# pisarnaInGarderoba-v2.net
KiCad netlist of a schematic drawn in EAGLE
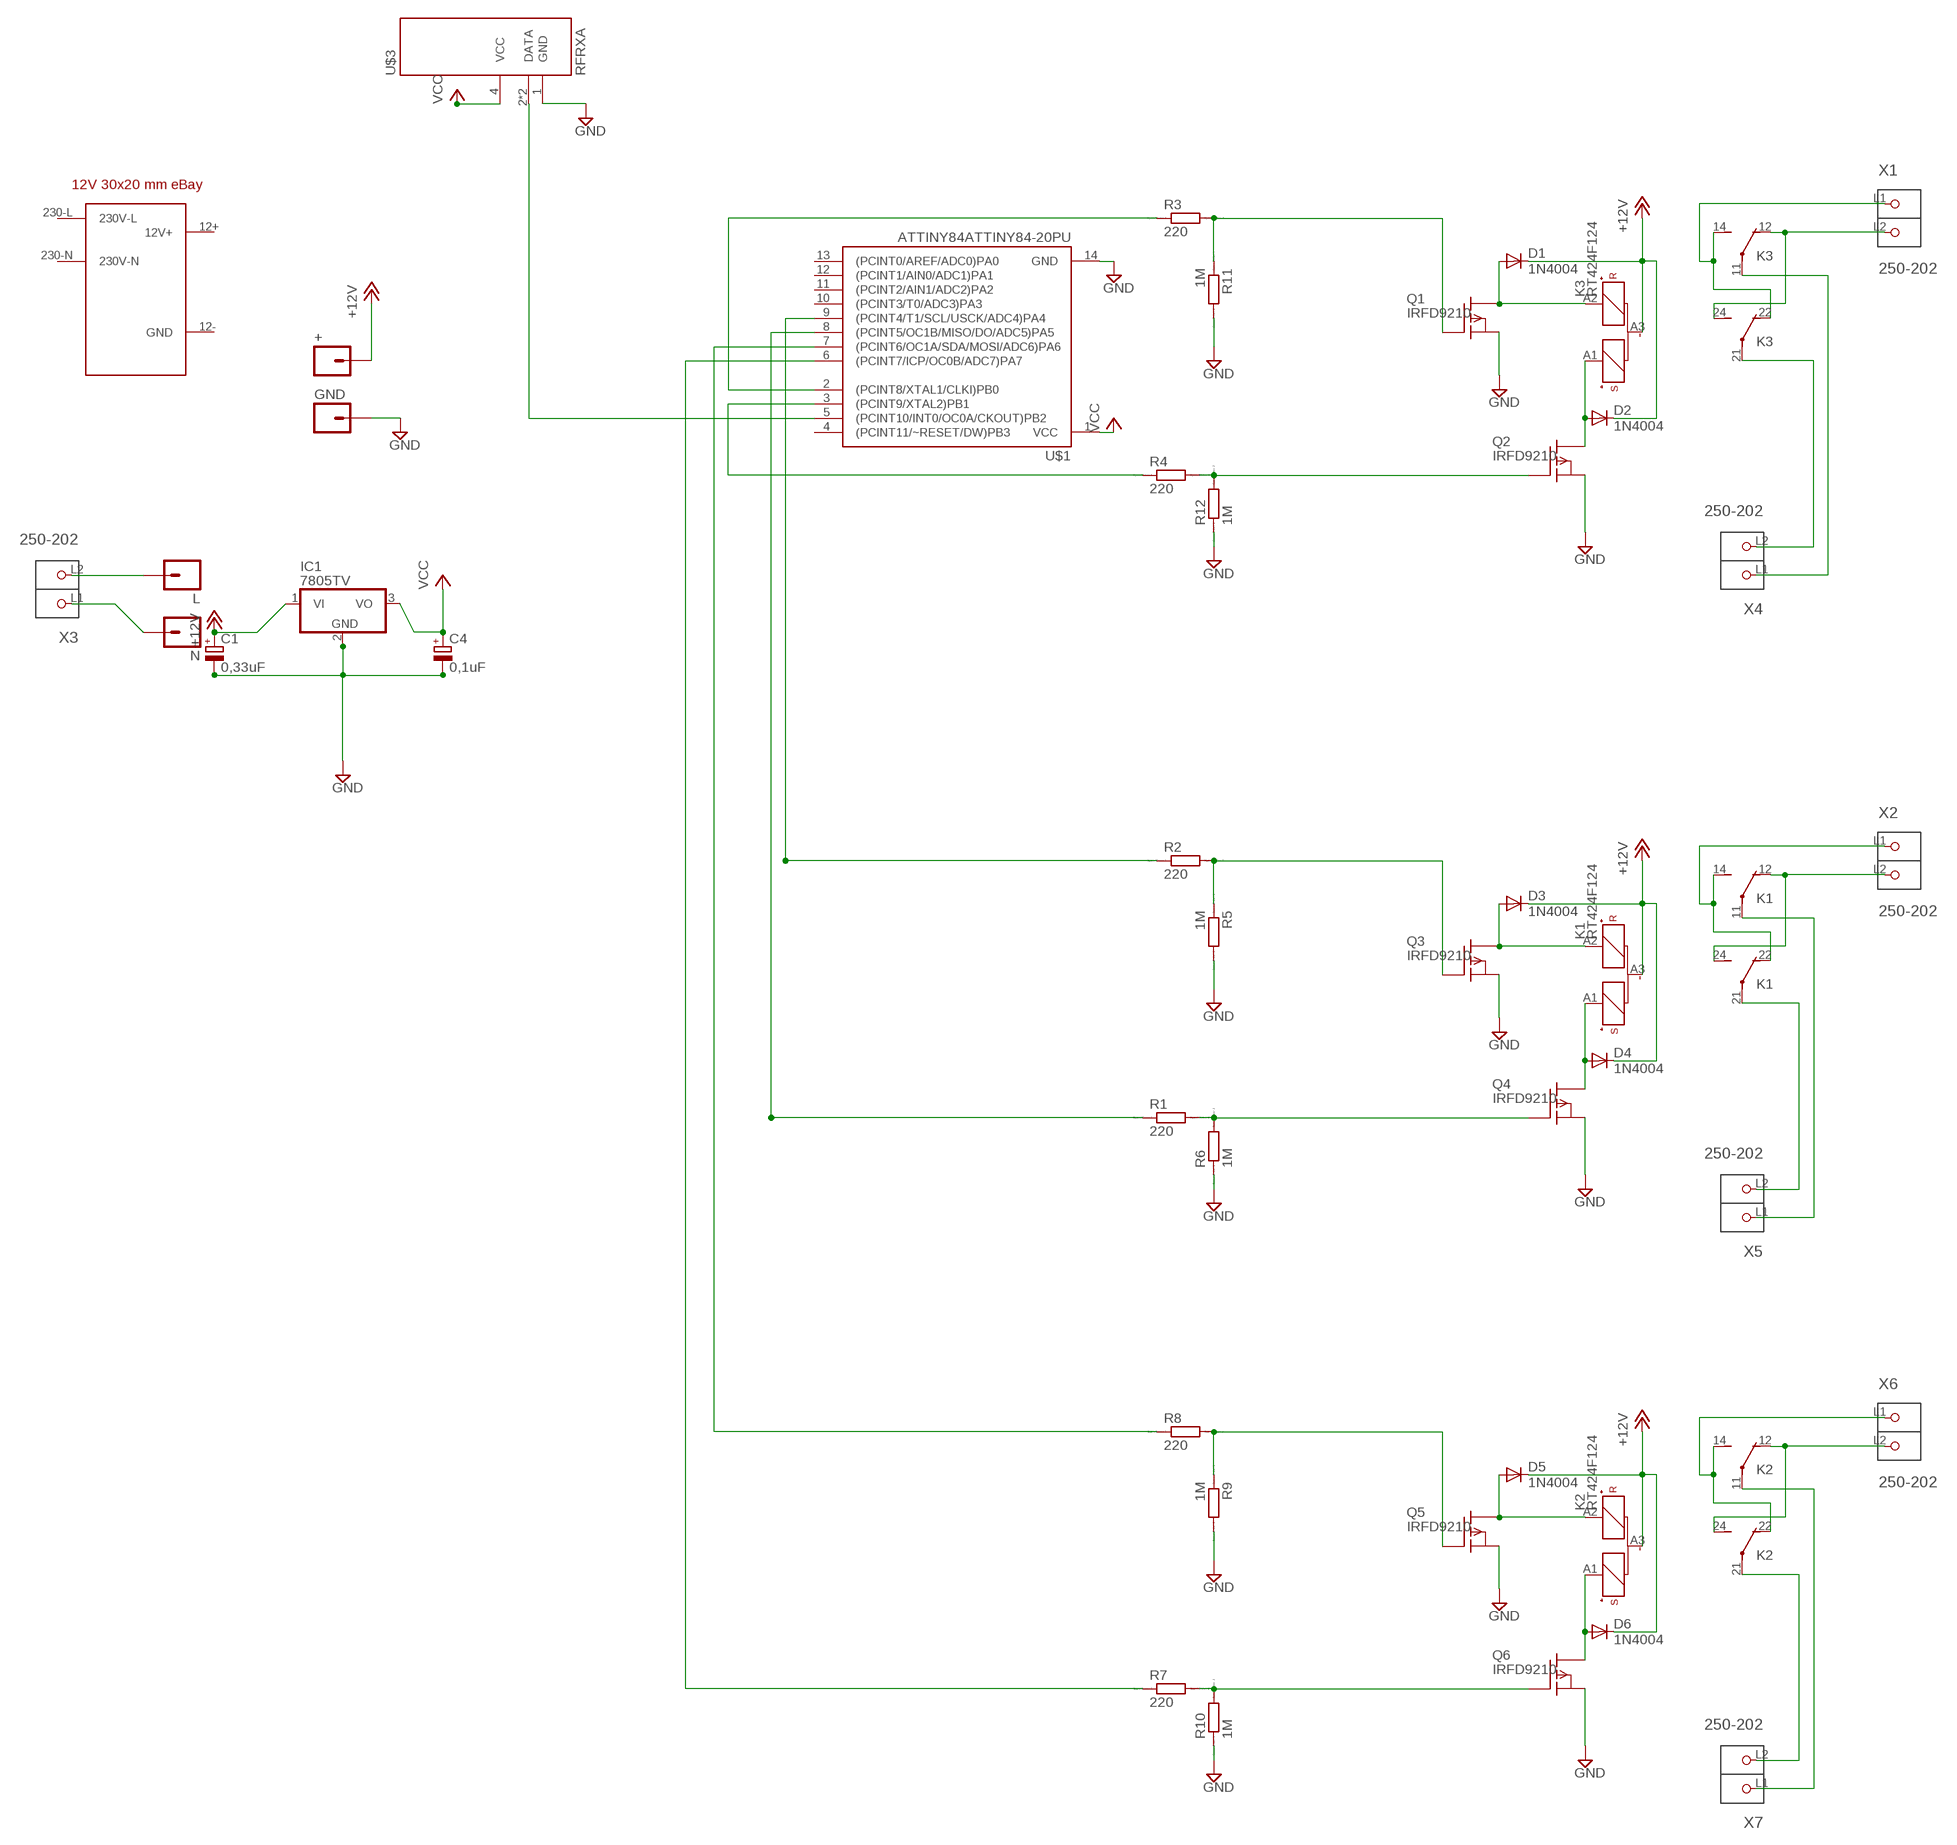
[diagram p0: schematic, sheet 1, part 1 of 2]
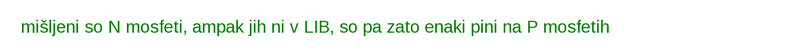
[diagram p1: schematic, sheet 1, part 2 of 2]

(export (version "E")
  (design (tool "Eeschema 10.0.6"))
  (components
    (comp (ref "+")
      (value "M01PTH")
      (footprint "eagle-import:1X01")
      (libsource (lib "eagle-import") (part "M01PTH"))
    )
    (comp (ref "C1")
      (value "0,33uF")
      (footprint "eagle-import:E2,5-5")
      (fields (field (name "MF") "SPC TECHNOLOGY") (field (name "MPN") "SPC15391"))
      (libsource (lib "eagle-import") (part "CPOL-EUE2.5-5"))
    )
    (comp (ref "C4")
      (value "0,1uF")
      (footprint "eagle-import:E2,5-5")
      (fields (field (name "MF") "SPC TECHNOLOGY") (field (name "MPN") "SPC15391"))
      (libsource (lib "eagle-import") (part "CPOL-EUE2.5-5"))
    )
    (comp (ref "D1")
      (value "1N4004")
      (footprint "eagle-import:DO41-10")
      (libsource (lib "eagle-import") (part "1N4004"))
    )
    (comp (ref "D2")
      (value "1N4004")
      (footprint "eagle-import:DO41-10")
      (libsource (lib "eagle-import") (part "1N4004"))
    )
    (comp (ref "D3")
      (value "1N4004")
      (footprint "eagle-import:DO41-10")
      (libsource (lib "eagle-import") (part "1N4004"))
    )
    (comp (ref "D4")
      (value "1N4004")
      (footprint "eagle-import:DO41-10")
      (libsource (lib "eagle-import") (part "1N4004"))
    )
    (comp (ref "D5")
      (value "1N4004")
      (footprint "eagle-import:DO41-10")
      (libsource (lib "eagle-import") (part "1N4004"))
    )
    (comp (ref "D6")
      (value "1N4004")
      (footprint "eagle-import:DO41-10")
      (libsource (lib "eagle-import") (part "1N4004"))
    )
    (comp (ref "GND")
      (value "M01PTH")
      (footprint "eagle-import:1X01")
      (libsource (lib "eagle-import") (part "M01PTH"))
    )
    (comp (ref "IC1")
      (value "7805TV")
      (footprint "eagle-import:TO220V")
      (libsource (lib "eagle-import") (part "78TV05"))
    )
    (comp (ref "K1")
      (value "RT424F124")
      (footprint "eagle-import:RT424")
      (libsource (lib "eagle-import") (part "RT424F412"))
    )
    (comp (ref "K2")
      (value "RT424F124")
      (footprint "eagle-import:RT424")
      (libsource (lib "eagle-import") (part "RT424F412"))
    )
    (comp (ref "K3")
      (value "RT424F124")
      (footprint "eagle-import:RT424")
      (libsource (lib "eagle-import") (part "RT424F412"))
    )
    (comp (ref "L")
      (value "M01PTH")
      (footprint "eagle-import:1X01")
      (libsource (lib "eagle-import") (part "M01PTH"))
    )
    (comp (ref "N")
      (value "M01PTH")
      (footprint "eagle-import:1X01")
      (libsource (lib "eagle-import") (part "M01PTH"))
    )
    (comp (ref "Q1")
      (value "IRFD9210")
      (footprint "eagle-import:DIL04")
      (libsource (lib "eagle-import") (part "IRFD9210"))
    )
    (comp (ref "Q2")
      (value "IRFD9210")
      (footprint "eagle-import:DIL04")
      (libsource (lib "eagle-import") (part "IRFD9210"))
    )
    (comp (ref "Q3")
      (value "IRFD9210")
      (footprint "eagle-import:DIL04")
      (libsource (lib "eagle-import") (part "IRFD9210"))
    )
    (comp (ref "Q4")
      (value "IRFD9210")
      (footprint "eagle-import:DIL04")
      (libsource (lib "eagle-import") (part "IRFD9210"))
    )
    (comp (ref "Q5")
      (value "IRFD9210")
      (footprint "eagle-import:DIL04")
      (libsource (lib "eagle-import") (part "IRFD9210"))
    )
    (comp (ref "Q6")
      (value "IRFD9210")
      (footprint "eagle-import:DIL04")
      (libsource (lib "eagle-import") (part "IRFD9210"))
    )
    (comp (ref "R1")
      (value "220")
      (footprint "eagle-import:0204_7")
      (libsource (lib "eagle-import") (part "R0204/7"))
    )
    (comp (ref "R2")
      (value "220")
      (footprint "eagle-import:0204_7")
      (libsource (lib "eagle-import") (part "R0204/7"))
    )
    (comp (ref "R3")
      (value "220")
      (footprint "eagle-import:0204_7")
      (libsource (lib "eagle-import") (part "R0204/7"))
    )
    (comp (ref "R4")
      (value "220")
      (footprint "eagle-import:0204_7")
      (libsource (lib "eagle-import") (part "R0204/7"))
    )
    (comp (ref "R5")
      (value "1M")
      (footprint "eagle-import:0204_7")
      (libsource (lib "eagle-import") (part "R0204/7"))
    )
    (comp (ref "R6")
      (value "1M")
      (footprint "eagle-import:0204_7")
      (libsource (lib "eagle-import") (part "R0204/7"))
    )
    (comp (ref "R7")
      (value "220")
      (footprint "eagle-import:0204_7")
      (libsource (lib "eagle-import") (part "R0204/7"))
    )
    (comp (ref "R8")
      (value "220")
      (footprint "eagle-import:0204_7")
      (libsource (lib "eagle-import") (part "R0204/7"))
    )
    (comp (ref "R9")
      (value "1M")
      (footprint "eagle-import:0204_7")
      (libsource (lib "eagle-import") (part "R0204/7"))
    )
    (comp (ref "R10")
      (value "1M")
      (footprint "eagle-import:0204_7")
      (libsource (lib "eagle-import") (part "R0204/7"))
    )
    (comp (ref "R11")
      (value "1M")
      (footprint "eagle-import:0204_7")
      (libsource (lib "eagle-import") (part "R0204/7"))
    )
    (comp (ref "R12")
      (value "1M")
      (footprint "eagle-import:0204_7")
      (libsource (lib "eagle-import") (part "R0204/7"))
    )
    (comp (ref "U$1")
      (value "ATTINY84ATTINY84-20PU")
      (footprint "eagle-import:DIL14")
      (libsource (lib "eagle-import") (part "ATTINY84ATTINY84-20PU"))
    )
    (comp (ref "U$2")
      (value "12V-30X20")
      (footprint "eagle-import:12V30X20")
      (libsource (lib "eagle-import") (part "12V-30X20"))
    )
    (comp (ref "U$3")
      (value "RFRXA")
      (footprint "eagle-import:IC")
      (libsource (lib "eagle-import") (part "RFRXA"))
    )
    (comp (ref "X1")
      (value "250-202")
      (footprint "eagle-import:P-250-202")
      (libsource (lib "eagle-import") (part "250-202"))
    )
    (comp (ref "X2")
      (value "250-202")
      (footprint "eagle-import:P-250-202")
      (libsource (lib "eagle-import") (part "250-202"))
    )
    (comp (ref "X3")
      (value "250-202")
      (footprint "eagle-import:P-250-202")
      (libsource (lib "eagle-import") (part "250-202"))
    )
    (comp (ref "X4")
      (value "250-202")
      (footprint "eagle-import:P-250-202")
      (libsource (lib "eagle-import") (part "250-202"))
    )
    (comp (ref "X5")
      (value "250-202")
      (footprint "eagle-import:P-250-202")
      (libsource (lib "eagle-import") (part "250-202"))
    )
    (comp (ref "X6")
      (value "250-202")
      (footprint "eagle-import:P-250-202")
      (libsource (lib "eagle-import") (part "250-202"))
    )
    (comp (ref "X7")
      (value "250-202")
      (footprint "eagle-import:P-250-202")
      (libsource (lib "eagle-import") (part "250-202"))
    )
  )
  (nets
    (net (code "1") (name "+12V") (class "Default")
      (node (ref "+") (pin "1") (pinfunction "1_1") (pintype "passive"))
      (node (ref "C1") (pin "+") (pinfunction "+_+") (pintype "passive"))
      (node (ref "D1") (pin "C") (pinfunction "C_C") (pintype "passive"))
      (node (ref "D2") (pin "C") (pinfunction "C_C") (pintype "passive"))
      (node (ref "D3") (pin "C") (pinfunction "C_C") (pintype "passive"))
      (node (ref "D4") (pin "C") (pinfunction "C_C") (pintype "passive"))
      (node (ref "D5") (pin "C") (pinfunction "C_C") (pintype "passive"))
      (node (ref "D6") (pin "C") (pinfunction "C_C") (pintype "passive"))
      (node (ref "IC1") (pin "1") (pinfunction "VI_1") (pintype "input"))
      (node (ref "K1") (pin "A3") (pinfunction "-_A3") (pintype "passive"))
      (node (ref "K2") (pin "A3") (pinfunction "-_A3") (pintype "passive"))
      (node (ref "K3") (pin "A3") (pinfunction "-_A3") (pintype "passive"))
    )
    (net (code "2") (name "GND") (class "Default")
      (node (ref "C1") (pin "-") (pinfunction "-_-") (pintype "passive"))
      (node (ref "C4") (pin "-") (pinfunction "-_-") (pintype "passive"))
      (node (ref "GND") (pin "1") (pinfunction "1_1") (pintype "passive"))
      (node (ref "IC1") (pin "2") (pinfunction "GND_2") (pintype "passive"))
      (node (ref "Q1") (pin "2") (pinfunction "S_2") (pintype "passive"))
      (node (ref "Q2") (pin "2") (pinfunction "S_2") (pintype "passive"))
      (node (ref "Q3") (pin "2") (pinfunction "S_2") (pintype "passive"))
      (node (ref "Q4") (pin "2") (pinfunction "S_2") (pintype "passive"))
      (node (ref "Q5") (pin "2") (pinfunction "S_2") (pintype "passive"))
      (node (ref "Q6") (pin "2") (pinfunction "S_2") (pintype "passive"))
      (node (ref "R10") (pin "1") (pinfunction "1_1") (pintype "passive"))
      (node (ref "R11") (pin "2") (pinfunction "2_2") (pintype "passive"))
      (node (ref "R12") (pin "1") (pinfunction "1_1") (pintype "passive"))
      (node (ref "R5") (pin "2") (pinfunction "2_2") (pintype "passive"))
      (node (ref "R6") (pin "1") (pinfunction "1_1") (pintype "passive"))
      (node (ref "R9") (pin "2") (pinfunction "2_2") (pintype "passive"))
      (node (ref "U$1") (pin "14") (pinfunction "GND_14") (pintype "bidirectional"))
      (node (ref "U$3") (pin "1") (pinfunction "GND_1") (pintype "bidirectional"))
    )
    (net (code "3") (name "Net-(K1A-R+)") (class "Default")
      (node (ref "D3") (pin "A") (pinfunction "A_A") (pintype "passive"))
      (node (ref "K1") (pin "A2") (pinfunction "R+_A2") (pintype "passive"))
      (node (ref "Q3") (pin "3") (pinfunction "D_3") (pintype "passive"))
      (node (ref "Q3") (pin "4") (pinfunction "D_4") (pintype "passive"))
    )
    (net (code "4") (name "Net-(K1A-S+)") (class "Default")
      (node (ref "D4") (pin "A") (pinfunction "A_A") (pintype "passive"))
      (node (ref "K1") (pin "A1") (pinfunction "S+_A1") (pintype "passive"))
      (node (ref "Q4") (pin "3") (pinfunction "D_3") (pintype "passive"))
      (node (ref "Q4") (pin "4") (pinfunction "D_4") (pintype "passive"))
    )
    (net (code "5") (name "Net-(K1B-O)") (class "Default")
      (node (ref "K1") (pin "12") (pinfunction "O_12") (pintype "passive"))
      (node (ref "K1") (pin "24") (pinfunction "S_24") (pintype "passive"))
      (node (ref "X2") (pin "L2") (pinfunction "P2_L2") (pintype "bidirectional"))
    )
    (net (code "6") (name "Net-(K1B-P)") (class "Default")
      (node (ref "K1") (pin "11") (pinfunction "P_11") (pintype "passive"))
      (node (ref "X5") (pin "L1") (pinfunction "P1_L1") (pintype "bidirectional"))
    )
    (net (code "7") (name "Net-(K1B-S)") (class "Default")
      (node (ref "K1") (pin "14") (pinfunction "S_14") (pintype "passive"))
      (node (ref "K1") (pin "22") (pinfunction "O_22") (pintype "passive"))
      (node (ref "X2") (pin "L1") (pinfunction "P1_L1") (pintype "bidirectional"))
    )
    (net (code "8") (name "Net-(K1C-P)") (class "Default")
      (node (ref "K1") (pin "21") (pinfunction "P_21") (pintype "passive"))
      (node (ref "X5") (pin "L2") (pinfunction "P2_L2") (pintype "bidirectional"))
    )
    (net (code "9") (name "Net-(K2A-R+)") (class "Default")
      (node (ref "D5") (pin "A") (pinfunction "A_A") (pintype "passive"))
      (node (ref "K2") (pin "A2") (pinfunction "R+_A2") (pintype "passive"))
      (node (ref "Q5") (pin "3") (pinfunction "D_3") (pintype "passive"))
      (node (ref "Q5") (pin "4") (pinfunction "D_4") (pintype "passive"))
    )
    (net (code "10") (name "Net-(K2A-S+)") (class "Default")
      (node (ref "D6") (pin "A") (pinfunction "A_A") (pintype "passive"))
      (node (ref "K2") (pin "A1") (pinfunction "S+_A1") (pintype "passive"))
      (node (ref "Q6") (pin "3") (pinfunction "D_3") (pintype "passive"))
      (node (ref "Q6") (pin "4") (pinfunction "D_4") (pintype "passive"))
    )
    (net (code "11") (name "Net-(K2B-O)") (class "Default")
      (node (ref "K2") (pin "12") (pinfunction "O_12") (pintype "passive"))
      (node (ref "K2") (pin "24") (pinfunction "S_24") (pintype "passive"))
      (node (ref "X6") (pin "L2") (pinfunction "P2_L2") (pintype "bidirectional"))
    )
    (net (code "12") (name "Net-(K2B-P)") (class "Default")
      (node (ref "K2") (pin "11") (pinfunction "P_11") (pintype "passive"))
      (node (ref "X7") (pin "L1") (pinfunction "P1_L1") (pintype "bidirectional"))
    )
    (net (code "13") (name "Net-(K2B-S)") (class "Default")
      (node (ref "K2") (pin "14") (pinfunction "S_14") (pintype "passive"))
      (node (ref "K2") (pin "22") (pinfunction "O_22") (pintype "passive"))
      (node (ref "X6") (pin "L1") (pinfunction "P1_L1") (pintype "bidirectional"))
    )
    (net (code "14") (name "Net-(K2C-P)") (class "Default")
      (node (ref "K2") (pin "21") (pinfunction "P_21") (pintype "passive"))
      (node (ref "X7") (pin "L2") (pinfunction "P2_L2") (pintype "bidirectional"))
    )
    (net (code "15") (name "Net-(K3A-R+)") (class "Default")
      (node (ref "D1") (pin "A") (pinfunction "A_A") (pintype "passive"))
      (node (ref "K3") (pin "A2") (pinfunction "R+_A2") (pintype "passive"))
      (node (ref "Q1") (pin "3") (pinfunction "D_3") (pintype "passive"))
      (node (ref "Q1") (pin "4") (pinfunction "D_4") (pintype "passive"))
    )
    (net (code "16") (name "Net-(K3A-S+)") (class "Default")
      (node (ref "D2") (pin "A") (pinfunction "A_A") (pintype "passive"))
      (node (ref "K3") (pin "A1") (pinfunction "S+_A1") (pintype "passive"))
      (node (ref "Q2") (pin "3") (pinfunction "D_3") (pintype "passive"))
      (node (ref "Q2") (pin "4") (pinfunction "D_4") (pintype "passive"))
    )
    (net (code "17") (name "Net-(K3B-O)") (class "Default")
      (node (ref "K3") (pin "12") (pinfunction "O_12") (pintype "passive"))
      (node (ref "K3") (pin "24") (pinfunction "S_24") (pintype "passive"))
      (node (ref "X1") (pin "L2") (pinfunction "P2_L2") (pintype "bidirectional"))
    )
    (net (code "18") (name "Net-(K3B-P)") (class "Default")
      (node (ref "K3") (pin "11") (pinfunction "P_11") (pintype "passive"))
      (node (ref "X4") (pin "L1") (pinfunction "P1_L1") (pintype "bidirectional"))
    )
    (net (code "19") (name "Net-(K3B-S)") (class "Default")
      (node (ref "K3") (pin "14") (pinfunction "S_14") (pintype "passive"))
      (node (ref "K3") (pin "22") (pinfunction "O_22") (pintype "passive"))
      (node (ref "X1") (pin "L1") (pinfunction "P1_L1") (pintype "bidirectional"))
    )
    (net (code "20") (name "Net-(K3C-P)") (class "Default")
      (node (ref "K3") (pin "21") (pinfunction "P_21") (pintype "passive"))
      (node (ref "X4") (pin "L2") (pinfunction "P2_L2") (pintype "bidirectional"))
    )
    (net (code "21") (name "Net-(Q1-G)") (class "Default")
      (node (ref "Q1") (pin "1") (pinfunction "G_1") (pintype "passive"))
      (node (ref "R11") (pin "1") (pinfunction "1_1") (pintype "passive"))
      (node (ref "R3") (pin "2") (pinfunction "2_2") (pintype "passive"))
    )
    (net (code "22") (name "Net-(Q2-G)") (class "Default")
      (node (ref "Q2") (pin "1") (pinfunction "G_1") (pintype "passive"))
      (node (ref "R12") (pin "2") (pinfunction "2_2") (pintype "passive"))
      (node (ref "R4") (pin "2") (pinfunction "2_2") (pintype "passive"))
    )
    (net (code "23") (name "Net-(Q3-G)") (class "Default")
      (node (ref "Q3") (pin "1") (pinfunction "G_1") (pintype "passive"))
      (node (ref "R2") (pin "2") (pinfunction "2_2") (pintype "passive"))
      (node (ref "R5") (pin "1") (pinfunction "1_1") (pintype "passive"))
    )
    (net (code "24") (name "Net-(Q4-G)") (class "Default")
      (node (ref "Q4") (pin "1") (pinfunction "G_1") (pintype "passive"))
      (node (ref "R1") (pin "2") (pinfunction "2_2") (pintype "passive"))
      (node (ref "R6") (pin "2") (pinfunction "2_2") (pintype "passive"))
    )
    (net (code "25") (name "Net-(Q5-G)") (class "Default")
      (node (ref "Q5") (pin "1") (pinfunction "G_1") (pintype "passive"))
      (node (ref "R8") (pin "2") (pinfunction "2_2") (pintype "passive"))
      (node (ref "R9") (pin "1") (pinfunction "1_1") (pintype "passive"))
    )
    (net (code "26") (name "Net-(Q6-G)") (class "Default")
      (node (ref "Q6") (pin "1") (pinfunction "G_1") (pintype "passive"))
      (node (ref "R10") (pin "2") (pinfunction "2_2") (pintype "passive"))
      (node (ref "R7") (pin "2") (pinfunction "2_2") (pintype "passive"))
    )
    (net (code "27") (name "Net-(U$1-(PCINT4{slash}T1{slash}SCL{slash}USCK{slash}ADC4)PA4)") (class "Default")
      (node (ref "R2") (pin "1") (pinfunction "1_1") (pintype "passive"))
      (node (ref "U$1") (pin "9") (pinfunction "(PCINT4/T1/SCL/USCK/ADC4)PA4_9") (pintype "bidirectional"))
    )
    (net (code "28") (name "Net-(U$1-(PCINT5{slash}OC1B{slash}MISO{slash}DO{slash}ADC5)PA5)") (class "Default")
      (node (ref "R1") (pin "1") (pinfunction "1_1") (pintype "passive"))
      (node (ref "U$1") (pin "8") (pinfunction "(PCINT5/OC1B/MISO/DO/ADC5)PA5_8") (pintype "bidirectional"))
    )
    (net (code "29") (name "Net-(U$1-(PCINT6{slash}OC1A{slash}SDA{slash}MOSI{slash}ADC6)PA6)") (class "Default")
      (node (ref "R8") (pin "1") (pinfunction "1_1") (pintype "passive"))
      (node (ref "U$1") (pin "7") (pinfunction "(PCINT6/OC1A/SDA/MOSI/ADC6)PA6_7") (pintype "bidirectional"))
    )
    (net (code "30") (name "Net-(U$1-(PCINT7{slash}ICP{slash}OC0B{slash}ADC7)PA7)") (class "Default")
      (node (ref "R7") (pin "1") (pinfunction "1_1") (pintype "passive"))
      (node (ref "U$1") (pin "6") (pinfunction "(PCINT7/ICP/OC0B/ADC7)PA7_6") (pintype "bidirectional"))
    )
    (net (code "31") (name "Net-(U$1-(PCINT8{slash}XTAL1{slash}CLKI)PB0)") (class "Default")
      (node (ref "R3") (pin "1") (pinfunction "1_1") (pintype "passive"))
      (node (ref "U$1") (pin "2") (pinfunction "(PCINT8/XTAL1/CLKI)PB0_2") (pintype "bidirectional"))
    )
    (net (code "32") (name "Net-(U$1-(PCINT9{slash}XTAL2)PB1)") (class "Default")
      (node (ref "R4") (pin "1") (pinfunction "1_1") (pintype "passive"))
      (node (ref "U$1") (pin "3") (pinfunction "(PCINT9/XTAL2)PB1_3") (pintype "bidirectional"))
    )
    (net (code "33") (name "Net-(U$1-(PCINT10{slash}INT0{slash}OC0A{slash}CKOUT)PB2)") (class "Default")
      (node (ref "U$1") (pin "5") (pinfunction "(PCINT10/INT0/OC0A/CKOUT)PB2_5") (pintype "bidirectional"))
      (node (ref "U$3") (pin "2") (pinfunction "DATA_2") (pintype "bidirectional"))
      (node (ref "U$3") (pin "3") (pinfunction "DATA_3") (pintype "bidirectional"))
    )
    (net (code "34") (name "Net-(X3-P1)") (class "Default")
      (node (ref "N") (pin "1") (pinfunction "1_1") (pintype "passive"))
      (node (ref "X3") (pin "L1") (pinfunction "P1_L1") (pintype "bidirectional"))
    )
    (net (code "35") (name "Net-(X3-P2)") (class "Default")
      (node (ref "L") (pin "1") (pinfunction "1_1") (pintype "passive"))
      (node (ref "X3") (pin "L2") (pinfunction "P2_L2") (pintype "bidirectional"))
    )
    (net (code "36") (name "VCC") (class "Default")
      (node (ref "C4") (pin "+") (pinfunction "+_+") (pintype "passive"))
      (node (ref "IC1") (pin "3") (pinfunction "VO_3") (pintype "passive"))
      (node (ref "U$1") (pin "1") (pinfunction "VCC_1") (pintype "bidirectional"))
      (node (ref "U$3") (pin "4") (pinfunction "VCC_4") (pintype "bidirectional"))
    )
    (net (code "37") (name "unconnected-(U$1-(PCINT0{slash}AREF{slash}ADC0)PA0-Pad13)") (class "Default")
      (node (ref "U$1") (pin "13") (pinfunction "(PCINT0/AREF/ADC0)PA0_13") (pintype "bidirectional"))
    )
    (net (code "38") (name "unconnected-(U$1-(PCINT1{slash}AIN0{slash}ADC1)PA1-Pad12)") (class "Default")
      (node (ref "U$1") (pin "12") (pinfunction "(PCINT1/AIN0/ADC1)PA1_12") (pintype "bidirectional"))
    )
    (net (code "39") (name "unconnected-(U$1-(PCINT2{slash}AIN1{slash}ADC2)PA2-Pad11)") (class "Default")
      (node (ref "U$1") (pin "11") (pinfunction "(PCINT2/AIN1/ADC2)PA2_11") (pintype "bidirectional"))
    )
    (net (code "40") (name "unconnected-(U$1-(PCINT3{slash}T0{slash}ADC3)PA3-Pad10)") (class "Default")
      (node (ref "U$1") (pin "10") (pinfunction "(PCINT3/T0/ADC3)PA3_10") (pintype "bidirectional"))
    )
    (net (code "41") (name "unconnected-(U$1-(PCINT11{slash}~{RESET{slash}DW})PB3-Pad4)") (class "Default")
      (node (ref "U$1") (pin "4") (pinfunction "(PCINT11/~{RESET/DW})PB3_4") (pintype "bidirectional"))
    )
    (net (code "42") (name "unconnected-(U$2-12V+-Pad12+)") (class "Default")
      (node (ref "U$2") (pin "12+") (pinfunction "12V+_12+") (pintype "bidirectional"))
    )
    (net (code "43") (name "unconnected-(U$2-230V-L-Pad230-L)") (class "Default")
      (node (ref "U$2") (pin "230-L") (pinfunction "230V-L_230-L") (pintype "bidirectional"))
    )
    (net (code "44") (name "unconnected-(U$2-230V-N-Pad230-N)") (class "Default")
      (node (ref "U$2") (pin "230-N") (pinfunction "230V-N_230-N") (pintype "bidirectional"))
    )
    (net (code "45") (name "unconnected-(U$2-GND-Pad12-)") (class "Default")
      (node (ref "U$2") (pin "12-") (pinfunction "GND_12-") (pintype "bidirectional"))
    )
  )
)
